# top_g.net
KiCad netlist of a schematic drawn in Altium Designer
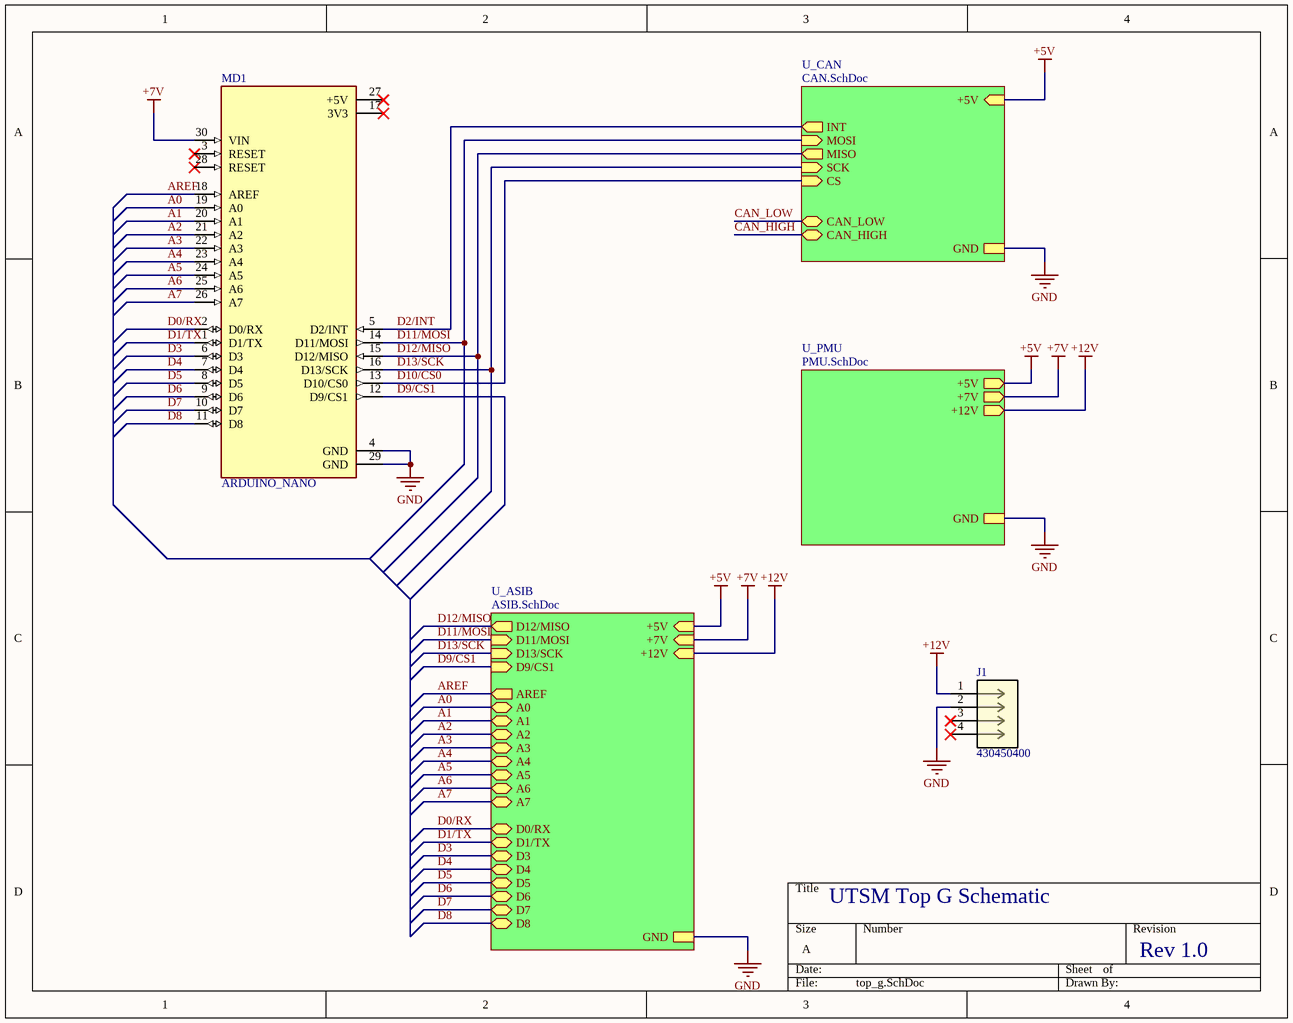
[diagram p0: top_g.SchDoc]

(export (version "E")
  (design (tool "Eeschema 10.0.6"))
  (components
    (comp (ref "J1")
      (value "430450400")
      (footprint "top_g:CON_430450400_MOL")
      (description "+12 from Battery")
      (libsource (lib "top_g") (part "430450400"))
    )
    (comp (ref "MD1")
      (value "ARDUINO_NANO")
      (footprint "SHIELD_ARDUINO_NANO")
      (description "Small, complete, and breadboard-friendly board based on the ATmega328 (Arduino Nano 3.x)")
      (fields (field (name "MP") "Arduino Nano") (field (name "MF") "Arduino"))
      (libsource (lib "top_g") (part "ARDUINO_NANO"))
    )
  )
  (nets
    (net (code "2") (name "+7V") (class "Default")
      (node (ref "MD1") (pin "30") (pinfunction "VIN_30") (pintype "input"))
    )
    (net (code "3") (name "+12V") (class "Default")
      (node (ref "J1") (pin "1") (pinfunction "1_1") (pintype "passive"))
    )
    (net (code "4") (name "/A0") (class "Default")
      (node (ref "MD1") (pin "19") (pinfunction "A0_19") (pintype "input"))
    )
    (net (code "5") (name "/A1") (class "Default")
      (node (ref "MD1") (pin "20") (pinfunction "A1_20") (pintype "input"))
    )
    (net (code "6") (name "/A2") (class "Default")
      (node (ref "MD1") (pin "21") (pinfunction "A2_21") (pintype "input"))
    )
    (net (code "7") (name "/A3") (class "Default")
      (node (ref "MD1") (pin "22") (pinfunction "A3_22") (pintype "input"))
    )
    (net (code "8") (name "/A4") (class "Default")
      (node (ref "MD1") (pin "23") (pinfunction "A4_23") (pintype "input"))
    )
    (net (code "9") (name "/A5") (class "Default")
      (node (ref "MD1") (pin "24") (pinfunction "A5_24") (pintype "input"))
    )
    (net (code "10") (name "/A6") (class "Default")
      (node (ref "MD1") (pin "25") (pinfunction "A6_25") (pintype "input"))
    )
    (net (code "11") (name "/A7") (class "Default")
      (node (ref "MD1") (pin "26") (pinfunction "A7_26") (pintype "input"))
    )
    (net (code "12") (name "/AREF") (class "Default")
      (node (ref "MD1") (pin "18") (pinfunction "AREF_18") (pintype "input"))
    )
    (net (code "15") (name "/D0{slash}RX") (class "Default")
      (node (ref "MD1") (pin "2") (pinfunction "D0/RX_2") (pintype "bidirectional"))
    )
    (net (code "16") (name "/D1{slash}TX") (class "Default")
      (node (ref "MD1") (pin "1") (pinfunction "D1/TX_1") (pintype "bidirectional"))
    )
    (net (code "17") (name "/D2{slash}INT") (class "Default")
      (node (ref "MD1") (pin "5") (pinfunction "D2/INT_5") (pintype "input"))
    )
    (net (code "18") (name "/D3") (class "Default")
      (node (ref "MD1") (pin "6") (pinfunction "D3_6") (pintype "bidirectional"))
    )
    (net (code "19") (name "/D4") (class "Default")
      (node (ref "MD1") (pin "7") (pinfunction "D4_7") (pintype "bidirectional"))
    )
    (net (code "20") (name "/D5") (class "Default")
      (node (ref "MD1") (pin "8") (pinfunction "D5_8") (pintype "bidirectional"))
    )
    (net (code "21") (name "/D6") (class "Default")
      (node (ref "MD1") (pin "9") (pinfunction "D6_9") (pintype "bidirectional"))
    )
    (net (code "22") (name "/D7") (class "Default")
      (node (ref "MD1") (pin "10") (pinfunction "D7_10") (pintype "bidirectional"))
    )
    (net (code "23") (name "/D8") (class "Default")
      (node (ref "MD1") (pin "11") (pinfunction "D8_11") (pintype "bidirectional"))
    )
    (net (code "24") (name "/D9{slash}CS1") (class "Default")
      (node (ref "MD1") (pin "12") (pinfunction "D9/CS1_12") (pintype "output"))
    )
    (net (code "25") (name "/D10{slash}CS0") (class "Default")
      (node (ref "MD1") (pin "13") (pinfunction "D10/CS0_13") (pintype "output"))
    )
    (net (code "26") (name "/D11{slash}MOSI") (class "Default")
      (node (ref "MD1") (pin "14") (pinfunction "D11/MOSI_14") (pintype "output"))
    )
    (net (code "27") (name "/D12{slash}MISO") (class "Default")
      (node (ref "MD1") (pin "15") (pinfunction "D12/MISO_15") (pintype "input"))
    )
    (net (code "28") (name "/D13{slash}SCK") (class "Default")
      (node (ref "MD1") (pin "16") (pinfunction "D13/SCK_16") (pintype "output"))
    )
    (net (code "29") (name "GND") (class "Default")
      (node (ref "J1") (pin "2") (pinfunction "2_2") (pintype "passive"))
      (node (ref "MD1") (pin "29") (pinfunction "GND_29") (pintype "power_in"))
      (node (ref "MD1") (pin "4") (pinfunction "GND_4") (pintype "power_in"))
    )
    (net (code "30") (name "unconnected-(J1-Pad3)") (class "Default")
      (node (ref "J1") (pin "3") (pinfunction "3_3") (pintype "passive+no_connect"))
    )
    (net (code "31") (name "unconnected-(J1-Pad4)") (class "Default")
      (node (ref "J1") (pin "4") (pinfunction "4_4") (pintype "passive+no_connect"))
    )
    (net (code "32") (name "unconnected-(MD1-+5V-Pad27)") (class "Default")
      (node (ref "MD1") (pin "27") (pinfunction "+5V_27") (pintype "power_in+no_connect"))
    )
    (net (code "33") (name "unconnected-(MD1-3V3-Pad17)") (class "Default")
      (node (ref "MD1") (pin "17") (pinfunction "3V3_17") (pintype "power_in+no_connect"))
    )
    (net (code "34") (name "unconnected-(MD1-RESET-Pad3)") (class "Default")
      (node (ref "MD1") (pin "3") (pinfunction "RESET_3") (pintype "input+no_connect"))
    )
    (net (code "35") (name "unconnected-(MD1-RESET-Pad28)") (class "Default")
      (node (ref "MD1") (pin "28") (pinfunction "RESET_28") (pintype "input+no_connect"))
    )
  )
)
